# 5V_12V_External.net
KiCad netlist of a schematic drawn in Altium Designer
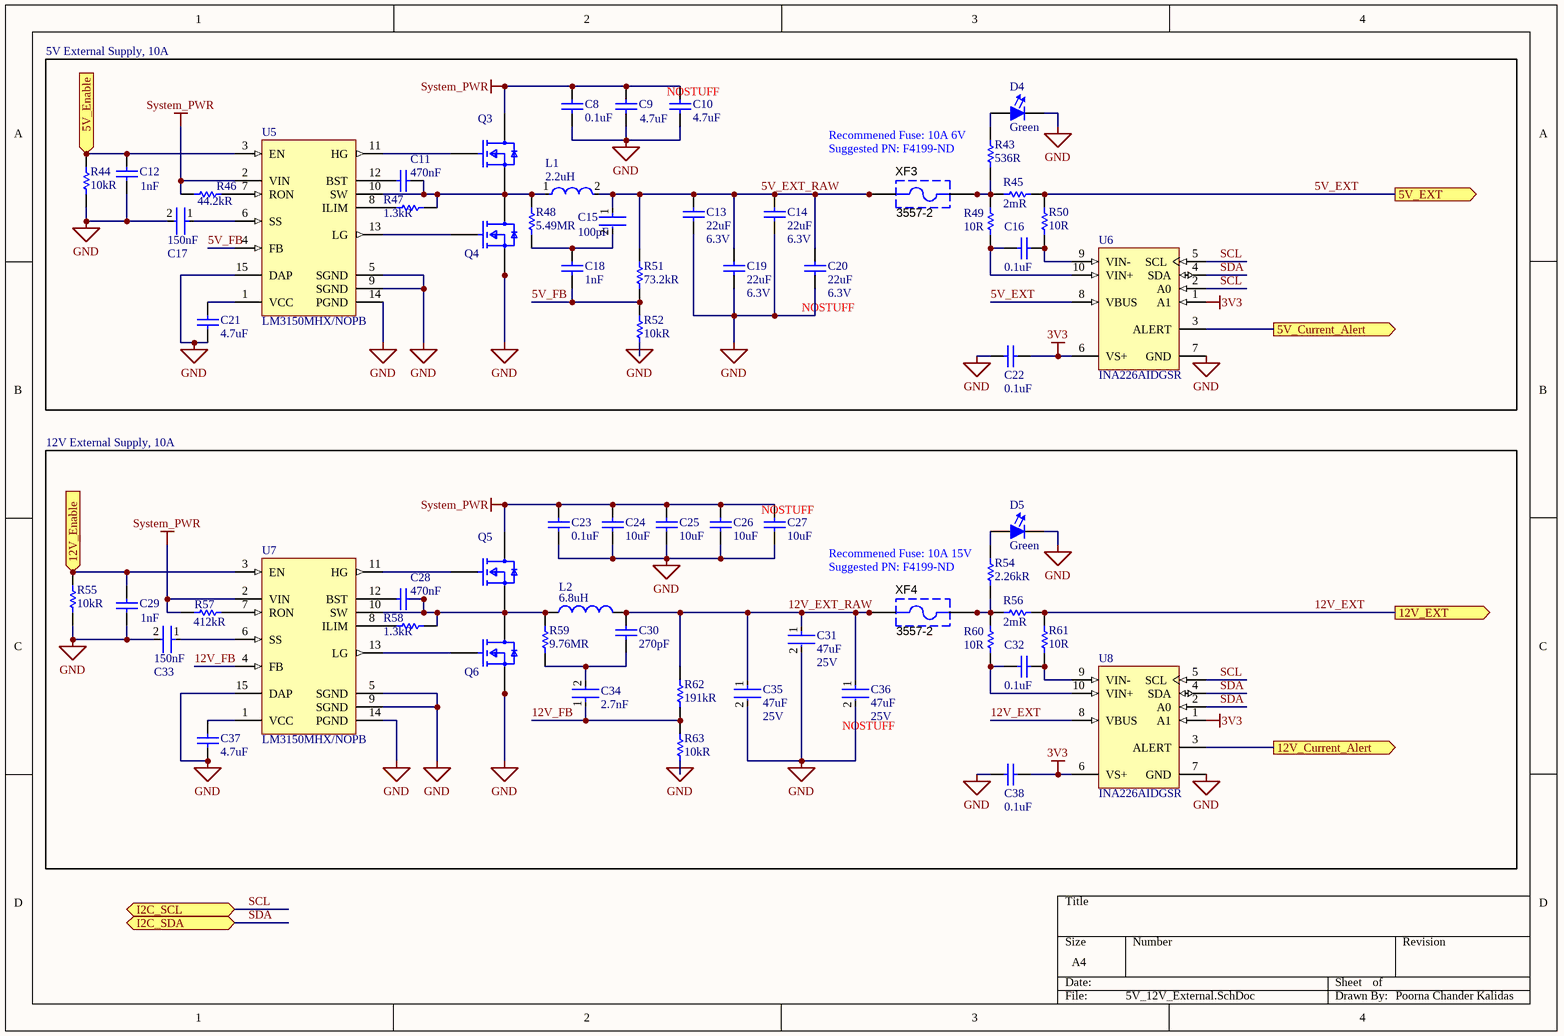
[diagram p0: 5V_12V_External.SchDoc]

(export (version "E")
  (design (tool "Eeschema 10.0.6"))
  (components
    (comp (ref "C8")
      (value "CL10B104JB8NNNC")
      (footprint "FP-CL10-0_1-IPC_A")
      (description "CAP CER 0.1UF 50V X7R 0603")
      (fields
        (field (name "TOLERANCE") "5%")
        (field (name "VOLTAGE") "50V")
        (field (name "CAPACITANCE") "0.1uF")
      )
      (libsource (lib "AUVIC") (part "CAP-NP-2"))
    )
    (comp (ref "C9")
      (value "CL31B475KBHNNNE")
      (footprint "CAPC3216X18N")
      (description "Capacitor 4.7 uF 50 VDC PU=2000 ST, CL31B475KBHNNNE, Samsung")
      (fields
        (field (name "VOLTAGE") "50V")
        (field (name "CAPACITANCE") "4.7uF")
        (field (name "TOLERANCE") "10%")
      )
      (libsource (lib "AUVIC") (part "CAP-NP-2"))
    )
    (comp (ref "C10")
      (value "CL31B475KBHNNNE")
      (footprint "CAPC3216X18N")
      (description "Capacitor 4.7 uF 50 VDC PU=2000 ST, CL31B475KBHNNNE, Samsung")
      (fields
        (field (name "VOLTAGE") "50V")
        (field (name "CAPACITANCE") "4.7uF")
        (field (name "TOLERANCE") "10%")
      )
      (libsource (lib "AUVIC") (part "CAP-NP-2"))
    )
    (comp (ref "C11")
      (value "470nF")
      (footprint "CAPC1608N(0603\")")
      (description "Capacitor, Ceramic, 50V, 10%, 0603 SMD, X7R")
      (fields
        (field (name "Comment") "470nF, 50V, 10%, 0603, Ceramic, SMD")
        (field (name "MADE BY") "Ashwin Sira")
        (field (name "PUBLISHER") "AUVic")
      )
      (libsource (lib "") (part "Symbol_2"))
    )
    (comp (ref "C12")
      (value "CL10B102KB8NNNC")
      (footprint "CAPC1608X90X30ML10T20")
      (description "Cap Ceramic 0.001uF 50V X7R 10% Pad SMD 0603 125°C T/R")
      (fields
        (field (name "TOLERANCE") "10%")
        (field (name "CAPACITANCE") "1nF")
        (field (name "VOLTAGE") "50V")
      )
      (libsource (lib "AUVIC") (part "CAP-NP-2"))
    )
    (comp (ref "C13")
      (value "GRM188R60J226MEA0D")
      (footprint "CAPC1608X90X35ML10T15")
      (fields
        (field (name "TOLERANCE") "20%")
        (field (name "CAPACITANCE") "22uF")
        (field (name "VOLTAGE RATING (DC)") "6.3V")
      )
      (libsource (lib "AUVIC") (part "CAP"))
    )
    (comp (ref "C14")
      (value "GRM188R60J226MEA0D")
      (footprint "CAPC1608X90X35ML10T15")
      (fields
        (field (name "TOLERANCE") "20%")
        (field (name "CAPACITANCE") "22uF")
        (field (name "VOLTAGE RATING (DC)") "6.3V")
      )
      (libsource (lib "AUVIC") (part "CAP"))
    )
    (comp (ref "C15")
      (value "CL10C101FB8NNNC")
      (footprint "FP-CL10-IPC_A")
      (description "Ceramic capacitor SMD 0603 100 pF 50 V 1 %")
      (fields
        (field (name "CAPACITANCE") "100pF")
        (field (name "VOLTAGE") "50V")
        (field (name "TOLERANCE") "1%")
      )
      (libsource (lib "AUVIC") (part "b4654b650e69147ec39a6b967a45e02"))
    )
    (comp (ref "C16")
      (value "CL10B104JB8NNNC")
      (footprint "FP-CL10-0_1-IPC_A")
      (description "CAP CER 0.1UF 50V X7R 0603")
      (fields
        (field (name "TOLERANCE") "5%")
        (field (name "VOLTAGE") "50V")
        (field (name "CAPACITANCE") "0.1uF")
      )
      (libsource (lib "AUVIC") (part "CAP-NP-2"))
    )
    (comp (ref "C17")
      (value "CL21B154KBFNNNG")
      (footprint "FP-CL21-IPC_A")
      (description "CAP CER 0.15UF 50V X7R 0805")
      (fields
        (field (name "TOLERANCE") "10%")
        (field (name "VOLTAGE") "50V")
        (field (name "CAPACITANCE") "150nF")
      )
      (libsource (lib "AUVIC") (part "b4654b650e69147ec39a6b967a45e02"))
    )
    (comp (ref "C18")
      (value "CL10B102KB8NNNC")
      (footprint "CAPC1608X90X30ML10T20")
      (description "Cap Ceramic 0.001uF 50V X7R 10% Pad SMD 0603 125°C T/R")
      (fields
        (field (name "TOLERANCE") "10%")
        (field (name "CAPACITANCE") "1nF")
        (field (name "VOLTAGE") "50V")
      )
      (libsource (lib "AUVIC") (part "CAP-NP-2"))
    )
    (comp (ref "C19")
      (value "GRM188R60J226MEA0D")
      (footprint "CAPC1608X90X35ML10T15")
      (fields
        (field (name "TOLERANCE") "20%")
        (field (name "CAPACITANCE") "22uF")
        (field (name "VOLTAGE RATING (DC)") "6.3V")
      )
      (libsource (lib "AUVIC") (part "CAP"))
    )
    (comp (ref "C20")
      (value "GRM188R60J226MEA0D")
      (footprint "CAPC1608X90X35ML10T15")
      (fields
        (field (name "TOLERANCE") "20%")
        (field (name "CAPACITANCE") "22uF")
        (field (name "VOLTAGE RATING (DC)") "6.3V")
      )
      (libsource (lib "AUVIC") (part "CAP"))
    )
    (comp (ref "C21")
      (value "CL31B475KBHNNNE")
      (footprint "CAPC3216X18N")
      (description "Capacitor 4.7 uF 50 VDC PU=2000 ST, CL31B475KBHNNNE, Samsung")
      (fields
        (field (name "VOLTAGE") "50V")
        (field (name "CAPACITANCE") "4.7uF")
        (field (name "TOLERANCE") "10%")
      )
      (libsource (lib "AUVIC") (part "CAP-NP-2"))
    )
    (comp (ref "C22")
      (value "CL10B104JB8NNNC")
      (footprint "FP-CL10-0_1-IPC_A")
      (description "CAP CER 0.1UF 50V X7R 0603")
      (fields
        (field (name "TOLERANCE") "5%")
        (field (name "VOLTAGE") "50V")
        (field (name "CAPACITANCE") "0.1uF")
      )
      (libsource (lib "AUVIC") (part "CAP-NP-2"))
    )
    (comp (ref "C23")
      (value "CL10B104JB8NNNC")
      (footprint "FP-CL10-0_1-IPC_A")
      (description "CAP CER 0.1UF 50V X7R 0603")
      (fields
        (field (name "TOLERANCE") "5%")
        (field (name "VOLTAGE") "50V")
        (field (name "CAPACITANCE") "0.1uF")
      )
      (libsource (lib "AUVIC") (part "CAP-NP-2"))
    )
    (comp (ref "C24")
      (value "CL31B106KBHNNNE")
      (footprint "CAPC3216X180X50ML20T30")
      (description "Cap Ceramic 10uF 50V X7R 10% Pad SMD 1206 125°C T/R")
      (fields (field (name "CAPACITANCE") "10uF") (field (name "TOLERANCE") "10%"))
      (libsource (lib "AUVIC") (part "CAP-NP-2"))
    )
    (comp (ref "C25")
      (value "CL31B106KBHNNNE")
      (footprint "CAPC3216X180X50ML20T30")
      (description "Cap Ceramic 10uF 50V X7R 10% Pad SMD 1206 125°C T/R")
      (fields (field (name "CAPACITANCE") "10uF") (field (name "TOLERANCE") "10%"))
      (libsource (lib "AUVIC") (part "CAP-NP-2"))
    )
    (comp (ref "C26")
      (value "CL31B106KBHNNNE")
      (footprint "CAPC3216X180X50ML20T30")
      (description "Cap Ceramic 10uF 50V X7R 10% Pad SMD 1206 125°C T/R")
      (fields (field (name "CAPACITANCE") "10uF") (field (name "TOLERANCE") "10%"))
      (libsource (lib "AUVIC") (part "CAP-NP-2"))
    )
    (comp (ref "C27")
      (value "CL31B106KBHNNNE")
      (footprint "CAPC3216X180X50ML20T30")
      (description "Cap Ceramic 10uF 50V X7R 10% Pad SMD 1206 125°C T/R")
      (fields (field (name "CAPACITANCE") "10uF") (field (name "TOLERANCE") "10%"))
      (libsource (lib "AUVIC") (part "CAP-NP-2"))
    )
    (comp (ref "C28")
      (value "470nF")
      (footprint "CAPC1608N(0603\")")
      (description "Capacitor, Ceramic, 50V, 10%, 0603 SMD, X7R")
      (fields
        (field (name "Comment") "470nF, 50V, 10%, 0603, Ceramic, SMD")
        (field (name "MADE BY") "Ashwin Sira")
        (field (name "PUBLISHER") "AUVic")
      )
      (libsource (lib "") (part "Symbol_2"))
    )
    (comp (ref "C29")
      (value "CL10B102KB8NNNC")
      (footprint "CAPC1608X90X30ML10T20")
      (description "Cap Ceramic 0.001uF 50V X7R 10% Pad SMD 0603 125°C T/R")
      (fields
        (field (name "TOLERANCE") "10%")
        (field (name "CAPACITANCE") "1nF")
        (field (name "VOLTAGE") "50V")
      )
      (libsource (lib "AUVIC") (part "CAP-NP-2"))
    )
    (comp (ref "C30")
      (value "GRM1885C2A271JA01D")
      (footprint "CAPC1608X90X35ML10T15")
      (description "CAP CER 270PF 100V C0G/NP0 0603")
      (fields (field (name "CAPACITANCE") "270pF") (field (name "TOLERANCE") "5%"))
      (libsource (lib "AUVIC") (part "CAP"))
    )
    (comp (ref "C31")
      (value "C3216X5R1E476M160AC")
      (footprint "FP-C3216-160-IPC_A")
      (fields
        (field (name "CAPACITANCE") "47uF")
        (field (name "VOLTAGE") "25V")
        (field (name "TOLERANCE") "20%")
      )
      (libsource (lib "AUVIC") (part "11868f565c42a9108669ba33697ecf6"))
    )
    (comp (ref "C32")
      (value "CL10B104JB8NNNC")
      (footprint "FP-CL10-0_1-IPC_A")
      (description "CAP CER 0.1UF 50V X7R 0603")
      (fields
        (field (name "TOLERANCE") "5%")
        (field (name "VOLTAGE") "50V")
        (field (name "CAPACITANCE") "0.1uF")
      )
      (libsource (lib "AUVIC") (part "CAP-NP-2"))
    )
    (comp (ref "C33")
      (value "CL21B154KBFNNNG")
      (footprint "FP-CL21-IPC_A")
      (description "CAP CER 0.15UF 50V X7R 0805")
      (fields
        (field (name "TOLERANCE") "10%")
        (field (name "VOLTAGE") "50V")
        (field (name "CAPACITANCE") "150nF")
      )
      (libsource (lib "AUVIC") (part "b4654b650e69147ec39a6b967a45e02"))
    )
    (comp (ref "C34")
      (value "CGA4C2C0G1H272J060AA")
      (footprint "FP-CGA4J-IPC_A")
      (description "CAP CER 2700PF 50V C0G 0805")
      (fields (field (name "CAPACITANCE") "2.7nF") (field (name "TOLERANCE") "5%"))
      (libsource (lib "AUVIC") (part "b4654b650e69147ec39a6b967a45e02"))
    )
    (comp (ref "C35")
      (value "C3216X5R1E476M160AC")
      (footprint "FP-C3216-160-IPC_A")
      (fields
        (field (name "CAPACITANCE") "47uF")
        (field (name "VOLTAGE") "25V")
        (field (name "TOLERANCE") "20%")
      )
      (libsource (lib "AUVIC") (part "11868f565c42a9108669ba33697ecf6"))
    )
    (comp (ref "C36")
      (value "C3216X5R1E476M160AC")
      (footprint "FP-C3216-160-IPC_A")
      (fields
        (field (name "CAPACITANCE") "47uF")
        (field (name "VOLTAGE") "25V")
        (field (name "TOLERANCE") "20%")
      )
      (libsource (lib "AUVIC") (part "11868f565c42a9108669ba33697ecf6"))
    )
    (comp (ref "C37")
      (value "CL31B475KBHNNNE")
      (footprint "CAPC3216X18N")
      (description "Capacitor 4.7 uF 50 VDC PU=2000 ST, CL31B475KBHNNNE, Samsung")
      (fields
        (field (name "VOLTAGE") "50V")
        (field (name "CAPACITANCE") "4.7uF")
        (field (name "TOLERANCE") "10%")
      )
      (libsource (lib "AUVIC") (part "CAP-NP-2"))
    )
    (comp (ref "C38")
      (value "CL10B104JB8NNNC")
      (footprint "FP-CL10-0_1-IPC_A")
      (description "CAP CER 0.1UF 50V X7R 0603")
      (fields
        (field (name "TOLERANCE") "5%")
        (field (name "VOLTAGE") "50V")
        (field (name "CAPACITANCE") "0.1uF")
      )
      (libsource (lib "AUVIC") (part "CAP-NP-2"))
    )
    (comp (ref "D4")
      (value "LT Q39G-Q1OO-25-1")
      (footprint "FP-LB_Q39E-MFG")
      (description "LED GREEN DIFFUSED 0603 SMD")
      (fields (field (name "COLOR") "Green"))
      (libsource (lib "") (part "Symbol_1"))
    )
    (comp (ref "D5")
      (value "LT Q39G-Q1OO-25-1")
      (footprint "FP-LB_Q39E-MFG")
      (description "LED GREEN DIFFUSED 0603 SMD")
      (fields (field (name "COLOR") "Green"))
      (libsource (lib "") (part "Symbol_1"))
    )
    (comp (ref "L1")
      (value "SRP1270-2R2M")
      (footprint "FP-SRP1270-MFG")
      (fields (field (name "TOLERANCE") "20%") (field (name "INDUCTANCE") "2.2uH"))
      (libsource (lib "AUVIC") (part "725321dda6339637d4d059423bc1c3c"))
    )
    (comp (ref "L2")
      (value "PG0936.682NL")
      (footprint "PG0936.682NL-Footprint-1")
      (description "Inductor Power Shielded Wirewound 6.8uH/5.4uH 20% 100KHz Ferrite 18A 0.0035Ohm DCR Automotive")
      (fields (field (name "INDUCTANCE") "6.8uH") (field (name "TOLERANCE") "20%"))
      (libsource (lib "AUVIC") (part "Symbol"))
    )
    (comp (ref "Q3")
      (value "IPC50N04S5L5R5ATMA1")
      (footprint "FP-DQJ0008A-MFG")
      (description "N-CHANNEL_30/40V")
      (libsource (lib "AUVIC") (part "372bcbff2a0099001efc4acc0eb9b45"))
    )
    (comp (ref "Q4")
      (value "IPC50N04S5L5R5ATMA1")
      (footprint "FP-DQJ0008A-MFG")
      (description "N-CHANNEL_30/40V")
      (libsource (lib "AUVIC") (part "372bcbff2a0099001efc4acc0eb9b45"))
    )
    (comp (ref "Q5")
      (value "IPC50N04S5L5R5ATMA1")
      (footprint "FP-DQJ0008A-MFG")
      (description "N-CHANNEL_30/40V")
      (libsource (lib "AUVIC") (part "372bcbff2a0099001efc4acc0eb9b45"))
    )
    (comp (ref "Q6")
      (value "IPC50N04S5L5R5ATMA1")
      (footprint "FP-DQJ0008A-MFG")
      (description "N-CHANNEL_30/40V")
      (libsource (lib "AUVIC") (part "372bcbff2a0099001efc4acc0eb9b45"))
    )
    (comp (ref "R43")
      (value "ERJ-3EKF5360V")
      (footprint "RESC1608X55X30ML15T15")
      (description "SMD Chip Resistor, 0603 [1608 Metric], 536 ohm, ERJ3EK Series, 75 V, Thick Film, 100 mW")
      (fields (field (name "RESISTANCE") "536R") (field (name "TOLERANCE") "1%"))
      (libsource (lib "AUVIC") (part "RES"))
    )
    (comp (ref "R44")
      (value "RC0603FR-0710KL")
      (footprint "RESC1608X55X25ML10T15")
      (description "Res General Purpose Thick Film 0603 10K Ohm 1% 1/10W ±100ppm/°C Molded SMD Paper T/R")
      (fields (field (name "RESISTANCE") "10kR") (field (name "TOLERANCE") "1%"))
      (libsource (lib "AUVIC") (part "RES-2"))
    )
    (comp (ref "R45")
      (value "CSR1206-0R002F1")
      (footprint "RESC2716X08N")
      (description "RES 0.002 OHM 1W 1% 1206")
      (fields (field (name "RESISTANCE") "2mR") (field (name "TOLERANCE") "1%"))
      (libsource (lib "AUVIC") (part "RES"))
    )
    (comp (ref "R46")
      (value "CRCW060344K2FKEA")
      (footprint "RESC1609X50X30ML10T20")
      (description "Res Thick Film 0603 44.2K Ohm 1% 0.1W(1/10W) ±100ppm/C Pad SMD Automotive T/R")
      (fields (field (name "TOLERANCE") "1%") (field (name "RESISTANCE") "44.2kR"))
      (libsource (lib "AUVIC") (part "RES"))
    )
    (comp (ref "R47")
      (value "CRCW06031K30FKEA")
      (footprint "RESC1609X50X30ML10T20")
      (description "Res Thick Film 0603 1.3K Ohm 1% 1/10W 100ppm/C Molded SMD SMD Paper T/R")
      (fields (field (name "RESISTANCE") "1.3kR") (field (name "TOLERANCE") "1%"))
      (libsource (lib "AUVIC") (part "RES"))
    )
    (comp (ref "R48")
      (value "CRCW06035M49FKEA")
      (footprint "RESC1608N(0603\")")
      (description "RES SMD 5.49M OHM 1% 1/10W 0603")
      (fields (field (name "RESISTANCE") "5.49MR") (field (name "TOLERANCE") "1%"))
      (libsource (lib "AUVIC") (part "RES"))
    )
    (comp (ref "R49")
      (value "ERJ3EKF10R0V")
      (footprint "FP-ERJ3EK-IPC_A")
      (fields (field (name "RESISTANCE") "10R") (field (name "TOLERANCE") "1%"))
      (libsource (lib "AUVIC") (part "RES"))
    )
    (comp (ref "R50")
      (value "ERJ3EKF10R0V")
      (footprint "FP-ERJ3EK-IPC_A")
      (fields (field (name "RESISTANCE") "10R") (field (name "TOLERANCE") "1%"))
      (libsource (lib "AUVIC") (part "RES"))
    )
    (comp (ref "R51")
      (value "ERJ-3EKF7322V")
      (footprint "RESC1608X55X30ML15T15")
      (description "Res Thick Film 0603 73.2K Ohm 1% 0.1W(1/10W) ±100ppm/C Pad SMD Automotive T/R")
      (fields (field (name "TOLERANCE") "1%") (field (name "RESISTANCE") "73.2kR"))
      (libsource (lib "AUVIC") (part "RES"))
    )
    (comp (ref "R52")
      (value "RC0603FR-0710KL")
      (footprint "RESC1608X55X25ML10T15")
      (description "Res General Purpose Thick Film 0603 10K Ohm 1% 1/10W ±100ppm/°C Molded SMD Paper T/R")
      (fields (field (name "RESISTANCE") "10kR") (field (name "TOLERANCE") "1%"))
      (libsource (lib "AUVIC") (part "RES-2"))
    )
    (comp (ref "R54")
      (value "RC0603FR-072K26L")
      (footprint "RESC0603(1608)_M")
      (description "RES SMD 2.26K OHM 1% 1/10W 0603")
      (fields (field (name "RESISTANCE") "2.26kR") (field (name "TOLERANCE") "1%"))
      (libsource (lib "AUVIC") (part "RES"))
    )
    (comp (ref "R55")
      (value "RC0603FR-0710KL")
      (footprint "RESC1608X55X25ML10T15")
      (description "Res General Purpose Thick Film 0603 10K Ohm 1% 1/10W ±100ppm/°C Molded SMD Paper T/R")
      (fields (field (name "RESISTANCE") "10kR") (field (name "TOLERANCE") "1%"))
      (libsource (lib "AUVIC") (part "RES-2"))
    )
    (comp (ref "R56")
      (value "CSR1206-0R002F1")
      (footprint "RESC2716X08N")
      (description "RES 0.002 OHM 1W 1% 1206")
      (fields (field (name "RESISTANCE") "2mR") (field (name "TOLERANCE") "1%"))
      (libsource (lib "AUVIC") (part "RES"))
    )
    (comp (ref "R57")
      (value "ERJ-3EKF4123V")
      (footprint "RESC1608X55X30ML15T15")
      (description "GLOVE, POLYAMIDE, L/FREE, PU, SIZE 6 - More Details")
      (fields (field (name "TOLERANCE") "1%") (field (name "RESISTANCE") "412kR"))
      (libsource (lib "AUVIC") (part "3mR"))
    )
    (comp (ref "R58")
      (value "CRCW06031K30FKEA")
      (footprint "RESC1609X50X30ML10T20")
      (description "Res Thick Film 0603 1.3K Ohm 1% 1/10W 100ppm/C Molded SMD SMD Paper T/R")
      (fields (field (name "RESISTANCE") "1.3kR") (field (name "TOLERANCE") "1%"))
      (libsource (lib "AUVIC") (part "RES"))
    )
    (comp (ref "R59")
      (value "CRCW06039M76FKEA")
      (footprint "RESC0603(1608)_M")
      (description "RES SMD 9.76M OHM 1% 1/10W 0603")
      (fields (field (name "TOLERANCE") "1%") (field (name "RESISTANCE") "9.76MR"))
      (libsource (lib "AUVIC") (part "RES"))
    )
    (comp (ref "R60")
      (value "ERJ3EKF10R0V")
      (footprint "FP-ERJ3EK-IPC_A")
      (fields (field (name "RESISTANCE") "10R") (field (name "TOLERANCE") "1%"))
      (libsource (lib "AUVIC") (part "RES"))
    )
    (comp (ref "R61")
      (value "ERJ3EKF10R0V")
      (footprint "FP-ERJ3EK-IPC_A")
      (fields (field (name "RESISTANCE") "10R") (field (name "TOLERANCE") "1%"))
      (libsource (lib "AUVIC") (part "RES"))
    )
    (comp (ref "R62")
      (value "ERJ-3EKF1913V")
      (footprint "RESC1608X55X30ML15T15")
      (description "RES, THICK FILM, 191KOHM, 0.1W, 0603")
      (fields (field (name "RESISTANCE") "191kR") (field (name "TOLERANCE") "1%"))
      (libsource (lib "AUVIC") (part "RES"))
    )
    (comp (ref "R63")
      (value "RC0603FR-0710KL")
      (footprint "RESC1608X55X25ML10T15")
      (description "Res General Purpose Thick Film 0603 10K Ohm 1% 1/10W ±100ppm/°C Molded SMD Paper T/R")
      (fields (field (name "RESISTANCE") "10kR") (field (name "TOLERANCE") "1%"))
      (libsource (lib "AUVIC") (part "RES-2"))
    )
    (comp (ref "U5")
      (value "LM3150MHX/NOPB")
      (footprint "PWP0014A_M")
      (description "IC REG CTRLR BUCK 14TSSOP")
      (libsource (lib "AUVIC") (part "PM-REG-LM3150MH"))
    )
    (comp (ref "U6")
      (value "INA226AIDGSR")
      (footprint "DGS0010A_M")
      (description "Bi Directional Current and Power Monitor 10-Pin VSSOP T/R")
      (libsource (lib "AUVIC") (part "TI-INA226DGS10"))
    )
    (comp (ref "U7")
      (value "LM3150MHX/NOPB")
      (footprint "PWP0014A_M")
      (description "IC REG CTRLR BUCK 14TSSOP")
      (libsource (lib "AUVIC") (part "PM-REG-LM3150MH"))
    )
    (comp (ref "U8")
      (value "INA226AIDGSR")
      (footprint "DGS0010A_M")
      (description "Bi Directional Current and Power Monitor 10-Pin VSSOP T/R")
      (libsource (lib "AUVIC") (part "TI-INA226DGS10"))
    )
    (comp (ref "XF3")
      (value "3557-2")
      (footprint "KSTN-3557-2")
      (description "Fuse Holder; Auto; 2 in1 Blade; THM; 1 Fuse; Vertical; 30 Amps")
      (fields (field (name "VOLTAGE") "500V"))
      (libsource (lib "AUVIC") (part "FUSE_HOLDER-4"))
    )
    (comp (ref "XF4")
      (value "3557-2")
      (footprint "KSTN-3557-2")
      (description "Fuse Holder; Auto; 2 in1 Blade; THM; 1 Fuse; Vertical; 30 Amps")
      (fields (field (name "VOLTAGE") "500V"))
      (libsource (lib "AUVIC") (part "FUSE_HOLDER-4"))
    )
  )
  (nets
    (net (code "1") (name "/5V_Current_Alert") (class "Default")
      (node (ref "U6") (pin "3") (pinfunction "ALERT_3") (pintype "open_collector"))
    )
    (net (code "2") (name "/5V_EXT") (class "Default")
      (node (ref "R45") (pin "1") (pinfunction "1_1") (pintype "passive"))
      (node (ref "R50") (pin "1") (pinfunction "1_1") (pintype "passive"))
      (node (ref "U6") (pin "8") (pinfunction "VBUS_8") (pintype "input"))
    )
    (net (code "3") (name "/5V_EXT_RAW") (class "Default")
      (node (ref "C13") (pin "1") (pinfunction "1_1") (pintype "passive"))
      (node (ref "C14") (pin "1") (pinfunction "1_1") (pintype "passive"))
      (node (ref "C15") (pin "1") (pinfunction "1_1") (pintype "passive"))
      (node (ref "C19") (pin "1") (pinfunction "1_1") (pintype "passive"))
      (node (ref "C20") (pin "1") (pinfunction "1_1") (pintype "passive"))
      (node (ref "L1") (pin "2") (pinfunction "2_2") (pintype "passive"))
      (node (ref "R51") (pin "1") (pinfunction "1_1") (pintype "passive"))
      (node (ref "XF3") (pin "1") (pinfunction "1_1") (pintype "passive"))
      (node (ref "XF3") (pin "2") (pinfunction "2_2") (pintype "passive"))
    )
    (net (code "4") (name "/5V_Enable") (class "Default")
      (node (ref "C12") (pin "2") (pinfunction "2_2") (pintype "passive"))
      (node (ref "R44") (pin "2") (pinfunction "2_2") (pintype "passive"))
      (node (ref "U5") (pin "3") (pinfunction "EN_3") (pintype "input"))
    )
    (net (code "5") (name "/5V_FB") (class "Default")
      (node (ref "C18") (pin "1") (pinfunction "1_1") (pintype "passive"))
      (node (ref "R51") (pin "2") (pinfunction "2_2") (pintype "passive"))
      (node (ref "R52") (pin "2") (pinfunction "2_2") (pintype "passive"))
      (node (ref "U5") (pin "4") (pinfunction "FB_4") (pintype "input"))
    )
    (net (code "6") (name "/12V_Current_Alert") (class "Default")
      (node (ref "U8") (pin "3") (pinfunction "ALERT_3") (pintype "open_collector"))
    )
    (net (code "7") (name "/12V_EXT") (class "Default")
      (node (ref "R56") (pin "1") (pinfunction "1_1") (pintype "passive"))
      (node (ref "R61") (pin "1") (pinfunction "1_1") (pintype "passive"))
      (node (ref "U8") (pin "8") (pinfunction "VBUS_8") (pintype "input"))
    )
    (net (code "8") (name "/12V_EXT_RAW") (class "Default")
      (node (ref "C30") (pin "1") (pinfunction "1_1") (pintype "passive"))
      (node (ref "C31") (pin "1") (pinfunction "1_1") (pintype "passive"))
      (node (ref "C35") (pin "1") (pinfunction "1_1") (pintype "passive"))
      (node (ref "C36") (pin "1") (pinfunction "1_1") (pintype "passive"))
      (node (ref "L2") (pin "2") (pinfunction "2_2") (pintype "passive"))
      (node (ref "R62") (pin "1") (pinfunction "1_1") (pintype "passive"))
      (node (ref "XF4") (pin "1") (pinfunction "1_1") (pintype "passive"))
      (node (ref "XF4") (pin "2") (pinfunction "2_2") (pintype "passive"))
    )
    (net (code "9") (name "/12V_Enable") (class "Default")
      (node (ref "C29") (pin "2") (pinfunction "2_2") (pintype "passive"))
      (node (ref "R55") (pin "2") (pinfunction "2_2") (pintype "passive"))
      (node (ref "U7") (pin "3") (pinfunction "EN_3") (pintype "input"))
    )
    (net (code "10") (name "/12V_FB") (class "Default")
      (node (ref "C34") (pin "1") (pinfunction "1_1") (pintype "passive"))
      (node (ref "R62") (pin "2") (pinfunction "2_2") (pintype "passive"))
      (node (ref "R63") (pin "2") (pinfunction "2_2") (pintype "passive"))
      (node (ref "U7") (pin "4") (pinfunction "FB_4") (pintype "input"))
    )
    (net (code "11") (name "/SCL") (class "Default")
      (node (ref "U6") (pin "2") (pinfunction "A0_2") (pintype "input"))
      (node (ref "U6") (pin "5") (pinfunction "SCL_5") (pintype "input"))
      (node (ref "U8") (pin "5") (pinfunction "SCL_5") (pintype "input"))
    )
    (net (code "12") (name "/SDA") (class "Default")
      (node (ref "U6") (pin "4") (pinfunction "SDA_4") (pintype "bidirectional"))
      (node (ref "U8") (pin "2") (pinfunction "A0_2") (pintype "input"))
      (node (ref "U8") (pin "4") (pinfunction "SDA_4") (pintype "bidirectional"))
    )
    (net (code "13") (name "3V3") (class "Default")
      (node (ref "C22") (pin "1") (pinfunction "1_1") (pintype "passive"))
      (node (ref "C38") (pin "1") (pinfunction "1_1") (pintype "passive"))
      (node (ref "U6") (pin "1") (pinfunction "A1_1") (pintype "input"))
      (node (ref "U6") (pin "6") (pinfunction "VS+_6") (pintype "power_in"))
      (node (ref "U8") (pin "1") (pinfunction "A1_1") (pintype "input"))
      (node (ref "U8") (pin "6") (pinfunction "VS+_6") (pintype "power_in"))
    )
    (net (code "14") (name "GND") (class "Default")
      (node (ref "C10") (pin "2") (pinfunction "2_2") (pintype "passive"))
      (node (ref "C12") (pin "1") (pinfunction "1_1") (pintype "passive"))
      (node (ref "C13") (pin "2") (pinfunction "2_2") (pintype "passive"))
      (node (ref "C14") (pin "2") (pinfunction "2_2") (pintype "passive"))
      (node (ref "C17") (pin "2") (pinfunction "2_2") (pintype "passive"))
      (node (ref "C19") (pin "2") (pinfunction "2_2") (pintype "passive"))
      (node (ref "C20") (pin "2") (pinfunction "2_2") (pintype "passive"))
      (node (ref "C21") (pin "1") (pinfunction "1_1") (pintype "passive"))
      (node (ref "C22") (pin "2") (pinfunction "2_2") (pintype "passive"))
      (node (ref "C23") (pin "1") (pinfunction "1_1") (pintype "passive"))
      (node (ref "C24") (pin "2") (pinfunction "2_2") (pintype "passive"))
      (node (ref "C25") (pin "2") (pinfunction "2_2") (pintype "passive"))
      (node (ref "C26") (pin "2") (pinfunction "2_2") (pintype "passive"))
      (node (ref "C27") (pin "2") (pinfunction "2_2") (pintype "passive"))
      (node (ref "C29") (pin "1") (pinfunction "1_1") (pintype "passive"))
      (node (ref "C31") (pin "2") (pinfunction "2_2") (pintype "passive"))
      (node (ref "C33") (pin "2") (pinfunction "2_2") (pintype "passive"))
      (node (ref "C35") (pin "2") (pinfunction "2_2") (pintype "passive"))
      (node (ref "C36") (pin "2") (pinfunction "2_2") (pintype "passive"))
      (node (ref "C37") (pin "1") (pinfunction "1_1") (pintype "passive"))
      (node (ref "C38") (pin "2") (pinfunction "2_2") (pintype "passive"))
      (node (ref "C8") (pin "1") (pinfunction "1_1") (pintype "passive"))
      (node (ref "C9") (pin "2") (pinfunction "2_2") (pintype "passive"))
      (node (ref "D4") (pin "1") (pinfunction "Cathode_1") (pintype "passive"))
      (node (ref "D5") (pin "1") (pinfunction "Cathode_1") (pintype "passive"))
      (node (ref "Q4") (pin "1") (pinfunction "S_1") (pintype "passive"))
      (node (ref "Q4") (pin "2") (pinfunction "S_2") (pintype "passive"))
      (node (ref "Q4") (pin "3") (pinfunction "S_3") (pintype "passive"))
      (node (ref "Q6") (pin "1") (pinfunction "S_1") (pintype "passive"))
      (node (ref "Q6") (pin "2") (pinfunction "S_2") (pintype "passive"))
      (node (ref "Q6") (pin "3") (pinfunction "S_3") (pintype "passive"))
      (node (ref "R44") (pin "1") (pinfunction "1_1") (pintype "passive"))
      (node (ref "R52") (pin "1") (pinfunction "1_1") (pintype "passive"))
      (node (ref "R55") (pin "1") (pinfunction "1_1") (pintype "passive"))
      (node (ref "R63") (pin "1") (pinfunction "1_1") (pintype "passive"))
      (node (ref "U5") (pin "14") (pinfunction "PGND_14") (pintype "power_in"))
      (node (ref "U5") (pin "15") (pinfunction "DAP_15") (pintype "power_in"))
      (node (ref "U5") (pin "5") (pinfunction "SGND_5") (pintype "power_in"))
      (node (ref "U5") (pin "9") (pinfunction "SGND_9") (pintype "power_in"))
      (node (ref "U6") (pin "7") (pinfunction "GND_7") (pintype "power_in"))
      (node (ref "U7") (pin "14") (pinfunction "PGND_14") (pintype "power_in"))
      (node (ref "U7") (pin "15") (pinfunction "DAP_15") (pintype "power_in"))
      (node (ref "U7") (pin "5") (pinfunction "SGND_5") (pintype "power_in"))
      (node (ref "U7") (pin "9") (pinfunction "SGND_9") (pintype "power_in"))
      (node (ref "U8") (pin "7") (pinfunction "GND_7") (pintype "power_in"))
    )
    (net (code "15") (name "Net-(C11-Anode)") (class "Default")
      (node (ref "C11") (pin "1") (pinfunction "Anode_1") (pintype "passive"))
      (node (ref "L1") (pin "1") (pinfunction "1_1") (pintype "passive"))
      (node (ref "Q3") (pin "1") (pinfunction "S_1") (pintype "passive"))
      (node (ref "Q3") (pin "2") (pinfunction "S_2") (pintype "passive"))
      (node (ref "Q3") (pin "3") (pinfunction "S_3") (pintype "passive"))
      (node (ref "Q4") (pin "5-6-7-8") (pinfunction "D_5-6-7-8") (pintype "passive"))
      (node (ref "R47") (pin "2") (pinfunction "2_2") (pintype "passive"))
      (node (ref "R48") (pin "1") (pinfunction "1_1") (pintype "passive"))
      (node (ref "U5") (pin "10") (pinfunction "SW_10") (pintype "power_in"))
    )
    (net (code "16") (name "Net-(C11-Cathode)") (class "Default")
      (node (ref "C11") (pin "2") (pinfunction "Cathode_2") (pintype "passive"))
      (node (ref "U5") (pin "12") (pinfunction "BST_12") (pintype "passive"))
    )
    (net (code "17") (name "Net-(C15-Pad2)") (class "Default")
      (node (ref "C15") (pin "2") (pinfunction "2_2") (pintype "passive"))
      (node (ref "C18") (pin "2") (pinfunction "2_2") (pintype "passive"))
      (node (ref "R48") (pin "2") (pinfunction "2_2") (pintype "passive"))
    )
    (net (code "18") (name "Net-(C28-Anode)") (class "Default")
      (node (ref "C28") (pin "1") (pinfunction "Anode_1") (pintype "passive"))
      (node (ref "L2") (pin "1") (pinfunction "1_1") (pintype "passive"))
      (node (ref "Q5") (pin "1") (pinfunction "S_1") (pintype "passive"))
      (node (ref "Q5") (pin "2") (pinfunction "S_2") (pintype "passive"))
      (node (ref "Q5") (pin "3") (pinfunction "S_3") (pintype "passive"))
      (node (ref "Q6") (pin "5-6-7-8") (pinfunction "D_5-6-7-8") (pintype "passive"))
      (node (ref "R58") (pin "2") (pinfunction "2_2") (pintype "passive"))
      (node (ref "R59") (pin "2") (pinfunction "2_2") (pintype "passive"))
      (node (ref "U7") (pin "10") (pinfunction "SW_10") (pintype "power_in"))
    )
    (net (code "19") (name "Net-(C28-Cathode)") (class "Default")
      (node (ref "C28") (pin "2") (pinfunction "Cathode_2") (pintype "passive"))
      (node (ref "U7") (pin "12") (pinfunction "BST_12") (pintype "passive"))
    )
    (net (code "20") (name "Net-(C30-Pad2)") (class "Default")
      (node (ref "C30") (pin "2") (pinfunction "2_2") (pintype "passive"))
      (node (ref "C34") (pin "2") (pinfunction "2_2") (pintype "passive"))
      (node (ref "R59") (pin "1") (pinfunction "1_1") (pintype "passive"))
    )
    (net (code "21") (name "Net-(D4-Anode)") (class "Default")
      (node (ref "D4") (pin "2") (pinfunction "Anode_2") (pintype "passive"))
      (node (ref "R43") (pin "2") (pinfunction "2_2") (pintype "passive"))
    )
    (net (code "22") (name "Net-(D5-Anode)") (class "Default")
      (node (ref "D5") (pin "2") (pinfunction "Anode_2") (pintype "passive"))
      (node (ref "R54") (pin "2") (pinfunction "2_2") (pintype "passive"))
    )
    (net (code "23") (name "Net-(Q3-G)") (class "Default")
      (node (ref "Q3") (pin "4") (pinfunction "G_4") (pintype "passive"))
      (node (ref "U5") (pin "11") (pinfunction "HG_11") (pintype "output"))
    )
    (net (code "24") (name "Net-(Q4-G)") (class "Default")
      (node (ref "Q4") (pin "4") (pinfunction "G_4") (pintype "passive"))
      (node (ref "U5") (pin "13") (pinfunction "LG_13") (pintype "output"))
    )
    (net (code "25") (name "Net-(Q5-G)") (class "Default")
      (node (ref "Q5") (pin "4") (pinfunction "G_4") (pintype "passive"))
      (node (ref "U7") (pin "11") (pinfunction "HG_11") (pintype "output"))
    )
    (net (code "26") (name "Net-(Q6-G)") (class "Default")
      (node (ref "Q6") (pin "4") (pinfunction "G_4") (pintype "passive"))
      (node (ref "U7") (pin "13") (pinfunction "LG_13") (pintype "output"))
    )
    (net (code "27") (name "Net-(R43-Pad1)") (class "Default")
      (node (ref "R43") (pin "1") (pinfunction "1_1") (pintype "passive"))
      (node (ref "R45") (pin "2") (pinfunction "2_2") (pintype "passive"))
      (node (ref "R49") (pin "1") (pinfunction "1_1") (pintype "passive"))
      (node (ref "XF3") (pin "3") (pinfunction "3_3") (pintype "passive"))
      (node (ref "XF3") (pin "4") (pinfunction "4_4") (pintype "passive"))
    )
    (net (code "28") (name "Net-(R54-Pad1)") (class "Default")
      (node (ref "R54") (pin "1") (pinfunction "1_1") (pintype "passive"))
      (node (ref "R56") (pin "2") (pinfunction "2_2") (pintype "passive"))
      (node (ref "R60") (pin "1") (pinfunction "1_1") (pintype "passive"))
      (node (ref "XF4") (pin "3") (pinfunction "3_3") (pintype "passive"))
      (node (ref "XF4") (pin "4") (pinfunction "4_4") (pintype "passive"))
    )
    (net (code "29") (name "Net-(U5-ILIM)") (class "Default")
      (node (ref "R47") (pin "1") (pinfunction "1_1") (pintype "passive"))
      (node (ref "U5") (pin "8") (pinfunction "ILIM_8") (pintype "passive"))
    )
    (net (code "30") (name "Net-(U5-RON)") (class "Default")
      (node (ref "R46") (pin "2") (pinfunction "2_2") (pintype "passive"))
      (node (ref "U5") (pin "7") (pinfunction "RON_7") (pintype "input"))
    )
    (net (code "31") (name "Net-(U5-SS)") (class "Default")
      (node (ref "C17") (pin "1") (pinfunction "1_1") (pintype "passive"))
      (node (ref "U5") (pin "6") (pinfunction "SS_6") (pintype "input"))
    )
    (net (code "32") (name "Net-(U5-VCC)") (class "Default")
      (node (ref "C21") (pin "2") (pinfunction "2_2") (pintype "passive"))
      (node (ref "U5") (pin "1") (pinfunction "VCC_1") (pintype "power_in"))
    )
    (net (code "33") (name "Net-(U6-VIN+)") (class "Default")
      (node (ref "C16") (pin "2") (pinfunction "2_2") (pintype "passive"))
      (node (ref "R49") (pin "2") (pinfunction "2_2") (pintype "passive"))
      (node (ref "U6") (pin "10") (pinfunction "VIN+_10") (pintype "input"))
    )
    (net (code "34") (name "Net-(U6-VIN-)") (class "Default")
      (node (ref "C16") (pin "1") (pinfunction "1_1") (pintype "passive"))
      (node (ref "R50") (pin "2") (pinfunction "2_2") (pintype "passive"))
      (node (ref "U6") (pin "9") (pinfunction "VIN-_9") (pintype "input"))
    )
    (net (code "35") (name "Net-(U7-ILIM)") (class "Default")
      (node (ref "R58") (pin "1") (pinfunction "1_1") (pintype "passive"))
      (node (ref "U7") (pin "8") (pinfunction "ILIM_8") (pintype "passive"))
    )
    (net (code "36") (name "Net-(U7-RON)") (class "Default")
      (node (ref "R57") (pin "1") (pinfunction "1_1") (pintype "passive"))
      (node (ref "U7") (pin "7") (pinfunction "RON_7") (pintype "input"))
    )
    (net (code "37") (name "Net-(U7-SS)") (class "Default")
      (node (ref "C33") (pin "1") (pinfunction "1_1") (pintype "passive"))
      (node (ref "U7") (pin "6") (pinfunction "SS_6") (pintype "input"))
    )
    (net (code "38") (name "Net-(U7-VCC)") (class "Default")
      (node (ref "C37") (pin "2") (pinfunction "2_2") (pintype "passive"))
      (node (ref "U7") (pin "1") (pinfunction "VCC_1") (pintype "power_in"))
    )
    (net (code "39") (name "Net-(U8-VIN+)") (class "Default")
      (node (ref "C32") (pin "2") (pinfunction "2_2") (pintype "passive"))
      (node (ref "R60") (pin "2") (pinfunction "2_2") (pintype "passive"))
      (node (ref "U8") (pin "10") (pinfunction "VIN+_10") (pintype "input"))
    )
    (net (code "40") (name "Net-(U8-VIN-)") (class "Default")
      (node (ref "C32") (pin "1") (pinfunction "1_1") (pintype "passive"))
      (node (ref "R61") (pin "2") (pinfunction "2_2") (pintype "passive"))
      (node (ref "U8") (pin "9") (pinfunction "VIN-_9") (pintype "input"))
    )
    (net (code "41") (name "System_PWR") (class "Default")
      (node (ref "C10") (pin "1") (pinfunction "1_1") (pintype "passive"))
      (node (ref "C23") (pin "2") (pinfunction "2_2") (pintype "passive"))
      (node (ref "C24") (pin "1") (pinfunction "1_1") (pintype "passive"))
      (node (ref "C25") (pin "1") (pinfunction "1_1") (pintype "passive"))
      (node (ref "C26") (pin "1") (pinfunction "1_1") (pintype "passive"))
      (node (ref "C27") (pin "1") (pinfunction "1_1") (pintype "passive"))
      (node (ref "C8") (pin "2") (pinfunction "2_2") (pintype "passive"))
      (node (ref "C9") (pin "1") (pinfunction "1_1") (pintype "passive"))
      (node (ref "Q3") (pin "5-6-7-8") (pinfunction "D_5-6-7-8") (pintype "passive"))
      (node (ref "Q5") (pin "5-6-7-8") (pinfunction "D_5-6-7-8") (pintype "passive"))
      (node (ref "R46") (pin "1") (pinfunction "1_1") (pintype "passive"))
      (node (ref "R57") (pin "2") (pinfunction "2_2") (pintype "passive"))
      (node (ref "U5") (pin "2") (pinfunction "VIN_2") (pintype "power_in"))
      (node (ref "U7") (pin "2") (pinfunction "VIN_2") (pintype "power_in"))
    )
  )
)
